# UniDie.net
KiCad netlist of a schematic drawn in EAGLE
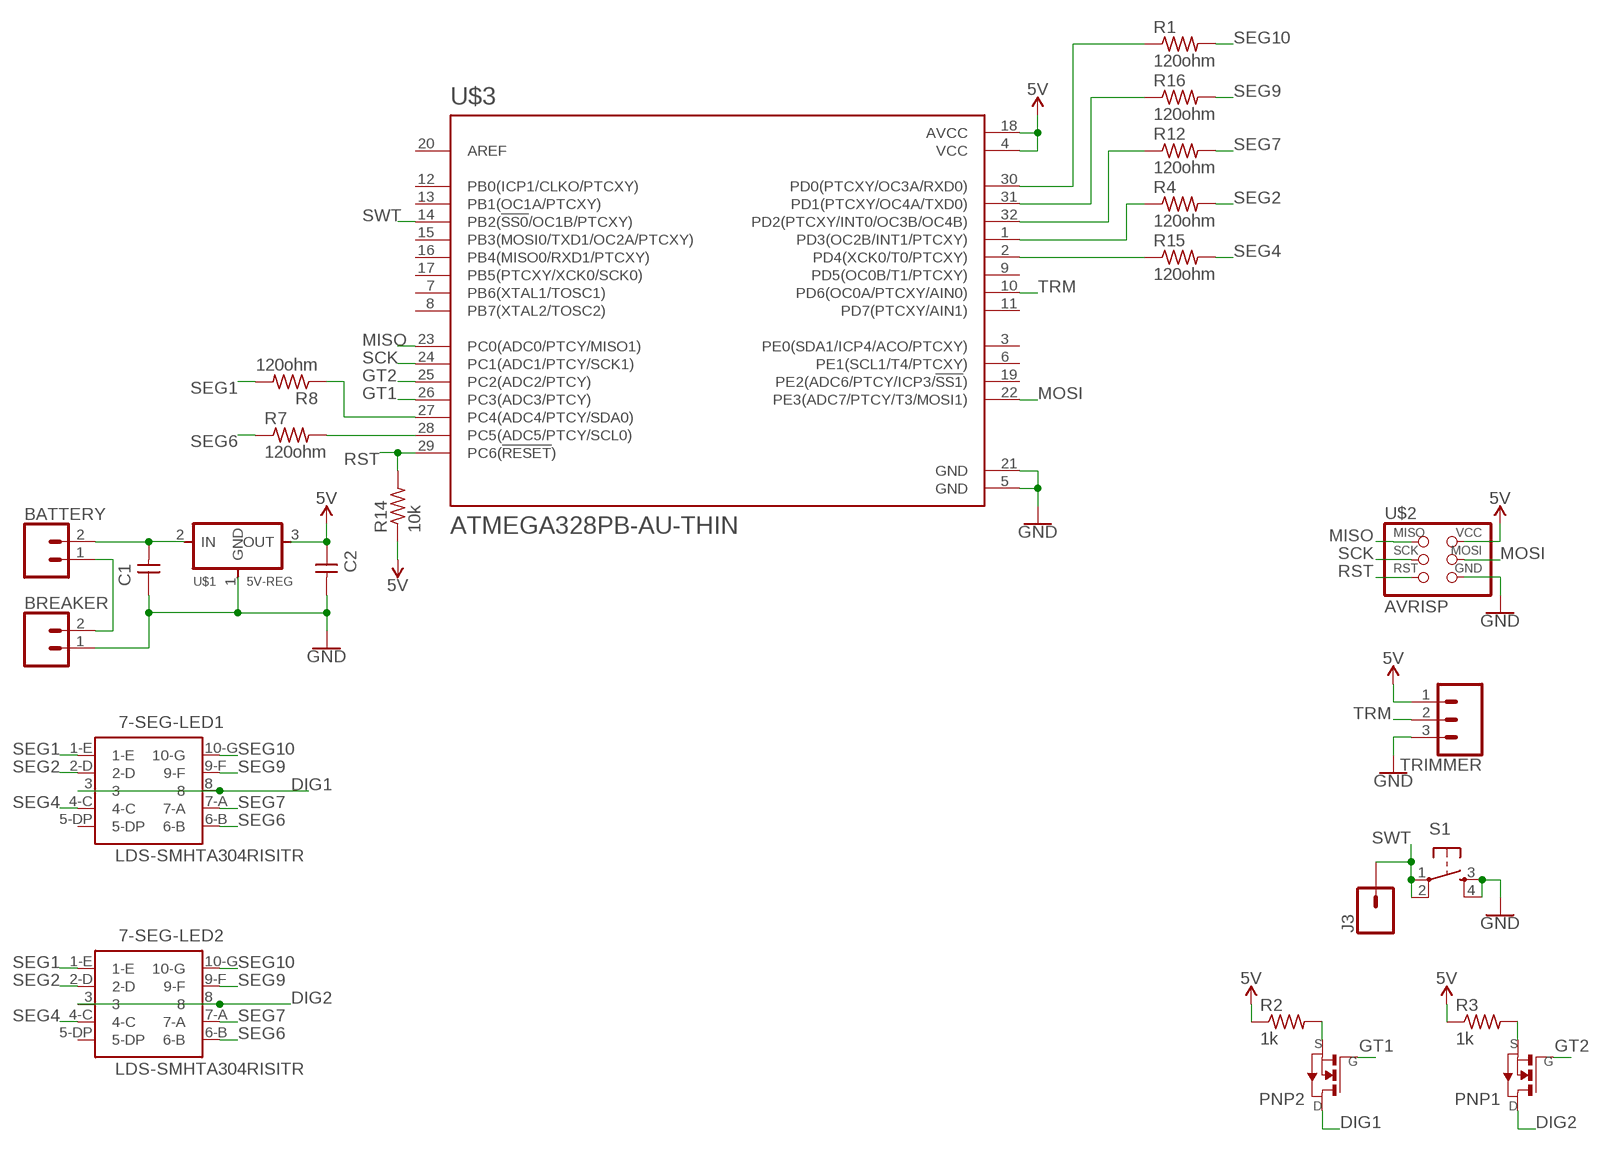
[diagram p0: schematic, sheet 1]

(export (version "E")
  (design (tool "Eeschema 10.0.6"))
  (components
    (comp (ref "7-SEG-LED1")
      (value "LDS-SMHTA304RISITR")
      (footprint "eagle-import:10-SMD")
      (libsource (lib "eagle-import") (part "LDS-SMHTA304RISITR"))
    )
    (comp (ref "7-SEG-LED2")
      (value "LDS-SMHTA304RISITR")
      (footprint "eagle-import:10-SMD")
      (libsource (lib "eagle-import") (part "LDS-SMHTA304RISITR"))
    )
    (comp (ref "BATTERY")
      (value "CONN_021X02_NO_SILK")
      (footprint "eagle-import:1X02_NO_SILK")
      (libsource (lib "eagle-import") (part "CONN_021X02_NO_SILK"))
    )
    (comp (ref "BREAKER")
      (value "CONN_021X02_NO_SILK")
      (footprint "eagle-import:1X02_NO_SILK")
      (libsource (lib "eagle-import") (part "CONN_021X02_NO_SILK"))
    )
    (comp (ref "C1")
      (value "CAP-UNPOLARIZEDFAB")
      (footprint "eagle-import:C1206FAB")
      (libsource (lib "eagle-import") (part "CAP-UNPOLARIZEDFAB"))
    )
    (comp (ref "C2")
      (value "CAP-UNPOLARIZEDFAB")
      (footprint "eagle-import:C1206FAB")
      (libsource (lib "eagle-import") (part "CAP-UNPOLARIZEDFAB"))
    )
    (comp (ref "J3")
      (value "CONN_01PTH_NO_SILK_YES_STOP")
      (footprint "eagle-import:1X01_NO_SILK")
      (libsource (lib "eagle-import") (part "CONN_01PTH_NO_SILK_YES_STOP"))
    )
    (comp (ref "PNP1")
      (value "NMOSFETSOT23")
      (footprint "eagle-import:SOT-23")
      (libsource (lib "eagle-import") (part "NMOSFETSOT23"))
    )
    (comp (ref "PNP2")
      (value "NMOSFETSOT23")
      (footprint "eagle-import:SOT-23")
      (libsource (lib "eagle-import") (part "NMOSFETSOT23"))
    )
    (comp (ref "R1")
      (value "120ohm")
      (footprint "eagle-import:R1206FAB")
      (libsource (lib "eagle-import") (part "RES-US1206FAB"))
    )
    (comp (ref "R2")
      (value "1k")
      (footprint "eagle-import:R1206FAB")
      (libsource (lib "eagle-import") (part "RES-US1206FAB"))
    )
    (comp (ref "R3")
      (value "1k")
      (footprint "eagle-import:R1206FAB")
      (libsource (lib "eagle-import") (part "RES-US1206FAB"))
    )
    (comp (ref "R4")
      (value "120ohm")
      (footprint "eagle-import:R1206FAB")
      (libsource (lib "eagle-import") (part "RES-US1206FAB"))
    )
    (comp (ref "R7")
      (value "120ohm")
      (footprint "eagle-import:R1206FAB")
      (libsource (lib "eagle-import") (part "RES-US1206FAB"))
    )
    (comp (ref "R8")
      (value "120ohm")
      (footprint "eagle-import:R1206FAB")
      (libsource (lib "eagle-import") (part "RES-US1206FAB"))
    )
    (comp (ref "R12")
      (value "120ohm")
      (footprint "eagle-import:R1206FAB")
      (libsource (lib "eagle-import") (part "RES-US1206FAB"))
    )
    (comp (ref "R14")
      (value "10k")
      (footprint "eagle-import:R1206FAB")
      (libsource (lib "eagle-import") (part "RES-US1206FAB"))
    )
    (comp (ref "R15")
      (value "120ohm")
      (footprint "eagle-import:R1206FAB")
      (libsource (lib "eagle-import") (part "RES-US1206FAB"))
    )
    (comp (ref "R16")
      (value "120ohm")
      (footprint "eagle-import:R1206FAB")
      (libsource (lib "eagle-import") (part "RES-US1206FAB"))
    )
    (comp (ref "S1")
      (value "6MM_SWITCH6MM_SWITCH")
      (footprint "eagle-import:6MM_SWITCH")
      (libsource (lib "eagle-import") (part "6MM_SWITCH6MM_SWITCH"))
    )
    (comp (ref "TRIMMER")
      (value "CONN_031X03_NO_SILK")
      (footprint "eagle-import:1X03_NO_SILK")
      (libsource (lib "eagle-import") (part "CONN_031X03_NO_SILK"))
    )
    (comp (ref "U$1")
      (value "5V-REG")
      (footprint "eagle-import:SOT-23")
      (libsource (lib "eagle-import") (part "5V-REG"))
    )
    (comp (ref "U$2")
      (value "AVRISP")
      (footprint "eagle-import:2X03")
      (libsource (lib "eagle-import") (part "AVRISP"))
    )
    (comp (ref "U$3")
      (value "ATMEGA328PB-AU-THIN")
      (footprint "eagle-import:TQFP32-08THIN")
      (libsource (lib "eagle-import") (part "ATMEGA328PB-AU-THIN"))
    )
  )
  (nets
    (net (code "1") (name "/DIG1") (class "Default")
      (node (ref "7-SEG-LED1") (pin "3") (pinfunction "3_3") (pintype "bidirectional"))
      (node (ref "7-SEG-LED1") (pin "8") (pinfunction "8_8") (pintype "bidirectional"))
      (node (ref "PNP2") (pin "1") (pinfunction "D_1") (pintype "passive"))
    )
    (net (code "2") (name "/DIG2") (class "Default")
      (node (ref "7-SEG-LED2") (pin "3") (pinfunction "3_3") (pintype "bidirectional"))
      (node (ref "7-SEG-LED2") (pin "8") (pinfunction "8_8") (pintype "bidirectional"))
      (node (ref "PNP1") (pin "1") (pinfunction "D_1") (pintype "passive"))
    )
    (net (code "3") (name "/GT1") (class "Default")
      (node (ref "PNP2") (pin "3") (pinfunction "G_3") (pintype "passive"))
      (node (ref "U$3") (pin "26") (pinfunction "PC3(ADC3/PTCY)_26") (pintype "bidirectional"))
    )
    (net (code "4") (name "/GT2") (class "Default")
      (node (ref "PNP1") (pin "3") (pinfunction "G_3") (pintype "passive"))
      (node (ref "U$3") (pin "25") (pinfunction "PC2(ADC2/PTCY)_25") (pintype "bidirectional"))
    )
    (net (code "5") (name "/MISO") (class "Default")
      (node (ref "U$2") (pin "1") (pinfunction "MISO_1") (pintype "passive"))
      (node (ref "U$3") (pin "23") (pinfunction "PC0(ADC0/PTCY/MISO1)_23") (pintype "bidirectional"))
    )
    (net (code "6") (name "/MOSI") (class "Default")
      (node (ref "U$2") (pin "4") (pinfunction "MOSI_4") (pintype "passive"))
      (node (ref "U$3") (pin "22") (pinfunction "PE3(ADC7/PTCY/T3/MOSI1)_22") (pintype "bidirectional"))
    )
    (net (code "7") (name "/RST") (class "Default")
      (node (ref "R14") (pin "2") (pinfunction "2_2") (pintype "passive"))
      (node (ref "U$2") (pin "5") (pinfunction "RST_5") (pintype "passive"))
      (node (ref "U$3") (pin "29") (pinfunction "PC6(~{RESET})_29") (pintype "bidirectional"))
    )
    (net (code "8") (name "/SCK") (class "Default")
      (node (ref "U$2") (pin "3") (pinfunction "SCK_3") (pintype "passive"))
      (node (ref "U$3") (pin "24") (pinfunction "PC1(ADC1/PTCY/SCK1)_24") (pintype "bidirectional"))
    )
    (net (code "9") (name "/SEG1") (class "Default")
      (node (ref "7-SEG-LED1") (pin "1-E") (pinfunction "1-E_1-E") (pintype "bidirectional"))
      (node (ref "7-SEG-LED2") (pin "1-E") (pinfunction "1-E_1-E") (pintype "bidirectional"))
      (node (ref "R8") (pin "2") (pinfunction "2_2") (pintype "passive"))
    )
    (net (code "10") (name "/SEG2") (class "Default")
      (node (ref "7-SEG-LED1") (pin "2-D") (pinfunction "2-D_2-D") (pintype "bidirectional"))
      (node (ref "7-SEG-LED2") (pin "2-D") (pinfunction "2-D_2-D") (pintype "bidirectional"))
      (node (ref "R4") (pin "2") (pinfunction "2_2") (pintype "passive"))
    )
    (net (code "11") (name "/SEG4") (class "Default")
      (node (ref "7-SEG-LED1") (pin "4-C") (pinfunction "4-C_4-C") (pintype "bidirectional"))
      (node (ref "7-SEG-LED2") (pin "4-C") (pinfunction "4-C_4-C") (pintype "bidirectional"))
      (node (ref "R15") (pin "2") (pinfunction "2_2") (pintype "passive"))
    )
    (net (code "12") (name "/SEG6") (class "Default")
      (node (ref "7-SEG-LED1") (pin "6-B") (pinfunction "6-B_6-B") (pintype "bidirectional"))
      (node (ref "7-SEG-LED2") (pin "6-B") (pinfunction "6-B_6-B") (pintype "bidirectional"))
      (node (ref "R7") (pin "1") (pinfunction "1_1") (pintype "passive"))
    )
    (net (code "13") (name "/SEG7") (class "Default")
      (node (ref "7-SEG-LED1") (pin "7-A") (pinfunction "7-A_7-A") (pintype "bidirectional"))
      (node (ref "7-SEG-LED2") (pin "7-A") (pinfunction "7-A_7-A") (pintype "bidirectional"))
      (node (ref "R12") (pin "2") (pinfunction "2_2") (pintype "passive"))
    )
    (net (code "14") (name "/SEG9") (class "Default")
      (node (ref "7-SEG-LED1") (pin "9-F") (pinfunction "9-F_9-F") (pintype "bidirectional"))
      (node (ref "7-SEG-LED2") (pin "9-F") (pinfunction "9-F_9-F") (pintype "bidirectional"))
      (node (ref "R16") (pin "2") (pinfunction "2_2") (pintype "passive"))
    )
    (net (code "15") (name "/SEG10") (class "Default")
      (node (ref "7-SEG-LED1") (pin "10-G") (pinfunction "10-G_10-G") (pintype "bidirectional"))
      (node (ref "7-SEG-LED2") (pin "10-G") (pinfunction "10-G_10-G") (pintype "bidirectional"))
      (node (ref "R1") (pin "2") (pinfunction "2_2") (pintype "passive"))
    )
    (net (code "16") (name "/SWT") (class "Default")
      (node (ref "J3") (pin "1") (pinfunction "1_1") (pintype "passive"))
      (node (ref "S1") (pin "1") (pinfunction "P_1") (pintype "passive"))
      (node (ref "S1") (pin "2") (pinfunction "P1_2") (pintype "passive"))
      (node (ref "U$3") (pin "14") (pinfunction "PB2(~{SS0}/OC1B/PTCXY)_14") (pintype "bidirectional"))
    )
    (net (code "17") (name "/TRM") (class "Default")
      (node (ref "TRIMMER") (pin "2") (pinfunction "2_2") (pintype "passive"))
      (node (ref "U$3") (pin "10") (pinfunction "PD6(OC0A/PTCXY/AIN0)_10") (pintype "bidirectional"))
    )
    (net (code "18") (name "5V") (class "Default")
      (node (ref "C2") (pin "1") (pinfunction "1_1") (pintype "passive"))
      (node (ref "R14") (pin "1") (pinfunction "1_1") (pintype "passive"))
      (node (ref "R2") (pin "1") (pinfunction "1_1") (pintype "passive"))
      (node (ref "R3") (pin "1") (pinfunction "1_1") (pintype "passive"))
      (node (ref "TRIMMER") (pin "1") (pinfunction "1_1") (pintype "passive"))
      (node (ref "U$1") (pin "3") (pinfunction "OUT_3") (pintype "output"))
      (node (ref "U$2") (pin "2") (pinfunction "VCC_2") (pintype "passive"))
      (node (ref "U$3") (pin "18") (pinfunction "AVCC_18") (pintype "power_in"))
      (node (ref "U$3") (pin "4") (pinfunction "VCC_4") (pintype "power_in"))
    )
    (net (code "19") (name "GND") (class "Default")
      (node (ref "BREAKER") (pin "1") (pinfunction "1_1") (pintype "passive"))
      (node (ref "C1") (pin "1") (pinfunction "1_1") (pintype "passive"))
      (node (ref "C2") (pin "2") (pinfunction "2_2") (pintype "passive"))
      (node (ref "S1") (pin "3") (pinfunction "S_3") (pintype "passive"))
      (node (ref "S1") (pin "4") (pinfunction "S1_4") (pintype "passive"))
      (node (ref "TRIMMER") (pin "3") (pinfunction "3_3") (pintype "passive"))
      (node (ref "U$1") (pin "1") (pinfunction "GND_1") (pintype "bidirectional"))
      (node (ref "U$2") (pin "6") (pinfunction "GND_6") (pintype "passive"))
      (node (ref "U$3") (pin "21") (pinfunction "GND_21") (pintype "power_in"))
      (node (ref "U$3") (pin "5") (pinfunction "GND_5") (pintype "power_in"))
    )
    (net (code "20") (name "Net-(BATTERY-Pad1)") (class "Default")
      (node (ref "BATTERY") (pin "1") (pinfunction "1_1") (pintype "passive"))
      (node (ref "BREAKER") (pin "2") (pinfunction "2_2") (pintype "passive"))
    )
    (net (code "21") (name "Net-(PNP1-S)") (class "Default")
      (node (ref "PNP1") (pin "2") (pinfunction "S_2") (pintype "passive"))
      (node (ref "R3") (pin "2") (pinfunction "2_2") (pintype "passive"))
    )
    (net (code "22") (name "Net-(PNP2-S)") (class "Default")
      (node (ref "PNP2") (pin "2") (pinfunction "S_2") (pintype "passive"))
      (node (ref "R2") (pin "2") (pinfunction "2_2") (pintype "passive"))
    )
    (net (code "23") (name "Net-(U$1-IN)") (class "Default")
      (node (ref "BATTERY") (pin "2") (pinfunction "2_2") (pintype "passive"))
      (node (ref "C1") (pin "2") (pinfunction "2_2") (pintype "passive"))
      (node (ref "U$1") (pin "2") (pinfunction "IN_2") (pintype "input"))
    )
    (net (code "24") (name "Net-(U$3-PC4(ADC4{slash}PTCY{slash}SDA0))") (class "Default")
      (node (ref "R8") (pin "1") (pinfunction "1_1") (pintype "passive"))
      (node (ref "U$3") (pin "27") (pinfunction "PC4(ADC4/PTCY/SDA0)_27") (pintype "bidirectional"))
    )
    (net (code "25") (name "Net-(U$3-PC5(ADC5{slash}PTCY{slash}SCL0))") (class "Default")
      (node (ref "R7") (pin "2") (pinfunction "2_2") (pintype "passive"))
      (node (ref "U$3") (pin "28") (pinfunction "PC5(ADC5/PTCY/SCL0)_28") (pintype "bidirectional"))
    )
    (net (code "26") (name "Net-(U$3-PD0(PTCXY{slash}OC3A{slash}RXD0))") (class "Default")
      (node (ref "R1") (pin "1") (pinfunction "1_1") (pintype "passive"))
      (node (ref "U$3") (pin "30") (pinfunction "PD0(PTCXY/OC3A/RXD0)_30") (pintype "bidirectional"))
    )
    (net (code "27") (name "Net-(U$3-PD1(PTCXY{slash}OC4A{slash}TXD0))") (class "Default")
      (node (ref "R16") (pin "1") (pinfunction "1_1") (pintype "passive"))
      (node (ref "U$3") (pin "31") (pinfunction "PD1(PTCXY/OC4A/TXD0)_31") (pintype "bidirectional"))
    )
    (net (code "28") (name "Net-(U$3-PD2(PTCXY{slash}INT0{slash}OC3B{slash}OC4B))") (class "Default")
      (node (ref "R12") (pin "1") (pinfunction "1_1") (pintype "passive"))
      (node (ref "U$3") (pin "32") (pinfunction "PD2(PTCXY/INT0/OC3B/OC4B)_32") (pintype "bidirectional"))
    )
    (net (code "29") (name "Net-(U$3-PD3(OC2B{slash}INT1{slash}PTCXY))") (class "Default")
      (node (ref "R4") (pin "1") (pinfunction "1_1") (pintype "passive"))
      (node (ref "U$3") (pin "1") (pinfunction "PD3(OC2B/INT1/PTCXY)_1") (pintype "bidirectional"))
    )
    (net (code "30") (name "Net-(U$3-PD4(XCK0{slash}T0{slash}PTCXY))") (class "Default")
      (node (ref "R15") (pin "1") (pinfunction "1_1") (pintype "passive"))
      (node (ref "U$3") (pin "2") (pinfunction "PD4(XCK0/T0/PTCXY)_2") (pintype "bidirectional"))
    )
    (net (code "31") (name "unconnected-(7-SEG-LED1-Pad5-DP)") (class "Default")
      (node (ref "7-SEG-LED1") (pin "5-DP") (pinfunction "5-DP_5-DP") (pintype "bidirectional"))
    )
    (net (code "32") (name "unconnected-(7-SEG-LED2-Pad5-DP)") (class "Default")
      (node (ref "7-SEG-LED2") (pin "5-DP") (pinfunction "5-DP_5-DP") (pintype "bidirectional"))
    )
    (net (code "33") (name "unconnected-(U$3-AREF-Pad20)") (class "Default")
      (node (ref "U$3") (pin "20") (pinfunction "AREF_20") (pintype "input"))
    )
    (net (code "34") (name "unconnected-(U$3-PB0(ICP1{slash}CLKO{slash}PTCXY)-Pad12)") (class "Default")
      (node (ref "U$3") (pin "12") (pinfunction "PB0(ICP1/CLKO/PTCXY)_12") (pintype "bidirectional"))
    )
    (net (code "35") (name "unconnected-(U$3-PB1(OC1A{slash}PTCXY)-Pad13)") (class "Default")
      (node (ref "U$3") (pin "13") (pinfunction "PB1(OC1A/PTCXY)_13") (pintype "bidirectional"))
    )
    (net (code "36") (name "unconnected-(U$3-PB3(MOSI0{slash}TXD1{slash}OC2A{slash}PTCXY)-Pad15)") (class "Default")
      (node (ref "U$3") (pin "15") (pinfunction "PB3(MOSI0/TXD1/OC2A/PTCXY)_15") (pintype "bidirectional"))
    )
    (net (code "37") (name "unconnected-(U$3-PB4(MISO0{slash}RXD1{slash}PTCXY)-Pad16)") (class "Default")
      (node (ref "U$3") (pin "16") (pinfunction "PB4(MISO0/RXD1/PTCXY)_16") (pintype "bidirectional"))
    )
    (net (code "38") (name "unconnected-(U$3-PB5(PTCXY{slash}XCK0{slash}SCK0)-Pad17)") (class "Default")
      (node (ref "U$3") (pin "17") (pinfunction "PB5(PTCXY/XCK0/SCK0)_17") (pintype "bidirectional"))
    )
    (net (code "39") (name "unconnected-(U$3-PB6(XTAL1{slash}TOSC1)-Pad7)") (class "Default")
      (node (ref "U$3") (pin "7") (pinfunction "PB6(XTAL1/TOSC1)_7") (pintype "bidirectional"))
    )
    (net (code "40") (name "unconnected-(U$3-PB7(XTAL2{slash}TOSC2)-Pad8)") (class "Default")
      (node (ref "U$3") (pin "8") (pinfunction "PB7(XTAL2/TOSC2)_8") (pintype "bidirectional"))
    )
    (net (code "41") (name "unconnected-(U$3-PD5(OC0B{slash}T1{slash}PTCXY)-Pad9)") (class "Default")
      (node (ref "U$3") (pin "9") (pinfunction "PD5(OC0B/T1/PTCXY)_9") (pintype "bidirectional"))
    )
    (net (code "42") (name "unconnected-(U$3-PD7(PTCXY{slash}AIN1)-Pad11)") (class "Default")
      (node (ref "U$3") (pin "11") (pinfunction "PD7(PTCXY/AIN1)_11") (pintype "bidirectional"))
    )
    (net (code "43") (name "unconnected-(U$3-PE0(SDA1{slash}ICP4{slash}ACO{slash}PTCXY)-Pad3)") (class "Default")
      (node (ref "U$3") (pin "3") (pinfunction "PE0(SDA1/ICP4/ACO/PTCXY)_3") (pintype "bidirectional"))
    )
    (net (code "44") (name "unconnected-(U$3-PE1(SCL1{slash}T4{slash}PTCXY)-Pad6)") (class "Default")
      (node (ref "U$3") (pin "6") (pinfunction "PE1(SCL1/T4/PTCXY)_6") (pintype "bidirectional"))
    )
    (net (code "45") (name "unconnected-(U$3-PE2(ADC6{slash}PTCY{slash}ICP3{slash}~{SS1})-Pad19)") (class "Default")
      (node (ref "U$3") (pin "19") (pinfunction "PE2(ADC6/PTCY/ICP3/~{SS1})_19") (pintype "bidirectional"))
    )
  )
)
